# LPEDT_revA1_bikeit_SENSOR.net
KiCad netlist of a schematic drawn in Altium Designer
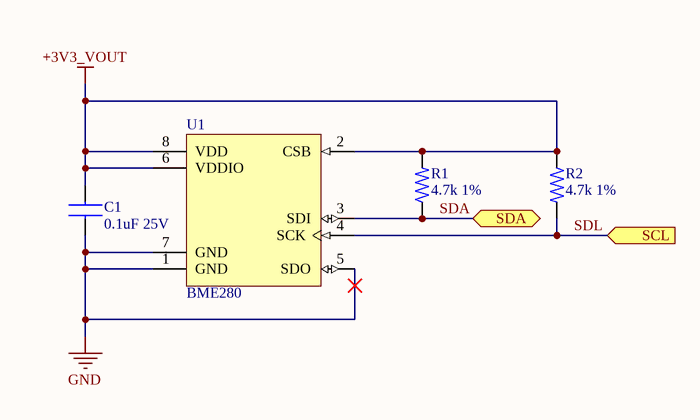
[diagram p0: LPEDT_revA1_bikeit_SENSOR.SchDoc]

(export (version "E")
  (design (tool "Eeschema 10.0.6"))
  (components
    (comp (ref "C1")
      (value "0.1uF 25V")
      (footprint "CAP_0603_1.60mm*0.80mm")
      (description "CAP CER 0.1UF 25V X7R 0603")
      (fields
        (field (name "MANUFACTURER") "Murata")
        (field (name "MANUFACTURER PART NUMBER") "GCJ188R71E104KA12D")
      )
      (libsource (lib "LPEDT_revA1_bikeit_IL") (part "GCJ188R71E104KA12D"))
    )
    (comp (ref "R1")
      (value "4.7k 1%")
      (footprint "RES_0603_1608X06")
      (description "RES SMD 4.7K OHM 1% 1/10W 0603")
      (fields
        (field (name "MANUFACTURER") "Yageo")
        (field (name "MANUFACTURER PART NUMBER") "RC0603FR-074K7L")
      )
      (libsource (lib "LPEDT_revA1_bikeit_IL") (part "RC0603FR-074K7L"))
    )
    (comp (ref "R2")
      (value "4.7k 1%")
      (footprint "RES_0603_1608X06")
      (description "RES SMD 4.7K OHM 1% 1/10W 0603")
      (fields
        (field (name "MANUFACTURER") "Yageo")
        (field (name "MANUFACTURER PART NUMBER") "RC0603FR-074K7L")
      )
      (libsource (lib "LPEDT_revA1_bikeit_IL") (part "RC0603FR-074K7L"))
    )
    (comp (ref "U1")
      (value "BME280")
      (footprint "PSON65P250X250X100-8N")
      (description "Humidity Temperature Sensor 0 ~ 100% RH I²C, SPI ±3% 1s Surface Mount")
      (fields (field (name "MF") "Bosch"))
      (libsource (lib "LPEDT_revA1_bikeit") (part "BME280"))
    )
  )
  (nets
    (net (code "1") (name "+3V3_VOUT") (class "Default")
      (node (ref "C1") (pin "1") (pinfunction "1_1") (pintype "passive"))
      (node (ref "R1") (pin "2") (pinfunction "2_2") (pintype "passive"))
      (node (ref "R2") (pin "1") (pinfunction "1_1") (pintype "passive"))
      (node (ref "U1") (pin "2") (pinfunction "CSB_2") (pintype "input"))
      (node (ref "U1") (pin "6") (pinfunction "VDDIO_6") (pintype "power_in"))
      (node (ref "U1") (pin "8") (pinfunction "VDD_8") (pintype "power_in"))
    )
    (net (code "2") (name "/SDA") (class "Default")
      (node (ref "R1") (pin "1") (pinfunction "1_1") (pintype "passive"))
      (node (ref "U1") (pin "3") (pinfunction "SDI_3") (pintype "bidirectional"))
    )
    (net (code "3") (name "/SDL") (class "Default")
      (node (ref "R2") (pin "2") (pinfunction "2_2") (pintype "passive"))
      (node (ref "U1") (pin "4") (pinfunction "SCK_4") (pintype "input"))
    )
    (net (code "4") (name "GND") (class "Default")
      (node (ref "C1") (pin "2") (pinfunction "2_2") (pintype "passive"))
      (node (ref "U1") (pin "1") (pinfunction "GND_1") (pintype "passive"))
      (node (ref "U1") (pin "5") (pinfunction "SDO_5") (pintype "bidirectional"))
      (node (ref "U1") (pin "7") (pinfunction "GND_7") (pintype "passive"))
    )
  )
)
